# MASTER.net
KiCad netlist of a schematic drawn in Altium Designer
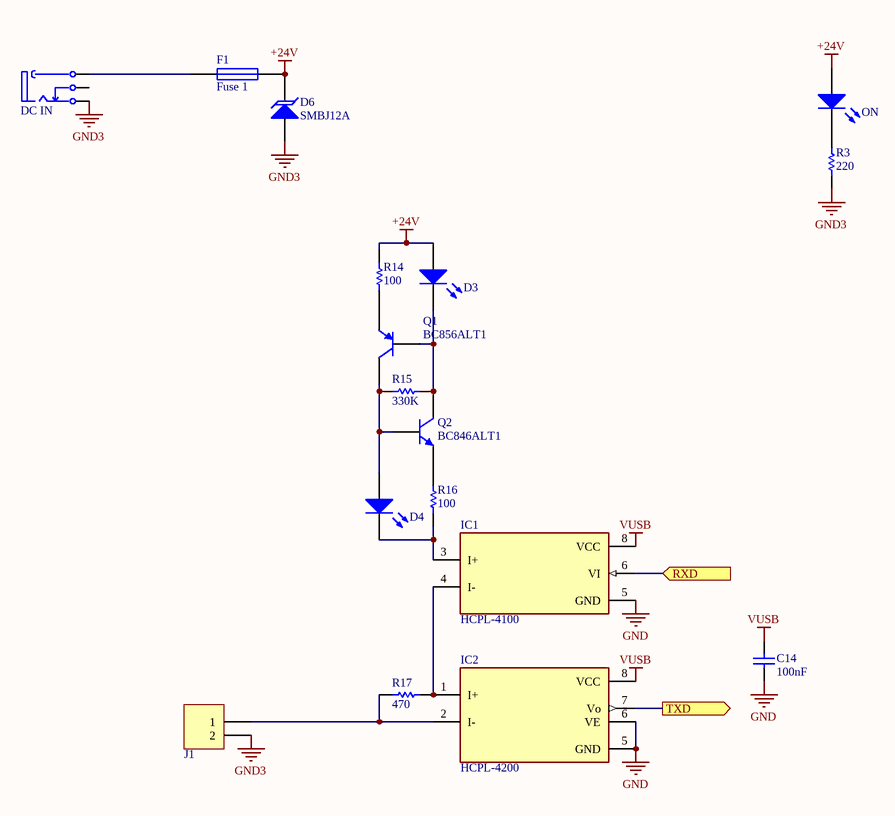
[diagram p0: MASTER.SchDoc]

(export (version "E")
  (design (tool "Eeschema 10.0.6"))
  (components
    (comp (ref "C14")
      (value "100nF")
      (footprint "C603")
      (description "Capacitor")
      (fields (field (name "DESIGNER") "Parsa Malekpour"))
      (libsource (lib "ParsaLibrary") (part "Cap"))
    )
    (comp (ref "D3") (value "LED") (footprint "LED-1206") (libsource (lib "ParsaLibrary") (part "LED")))
    (comp (ref "D4") (value "LED") (footprint "LED-1206") (libsource (lib "ParsaLibrary") (part "LED")))
    (comp (ref "D6")
      (value "SMBJ12A")
      (footprint "DO-214AA")
      (description "Surface Mount Transient Voltage Suppressors Diode")
      (libsource (lib "ParsaLibrary") (part "SMBJxxA"))
    )
    (comp (ref "DC IN")
      (value "JACK")
      (footprint "jack-dc")
      (libsource (lib "ParsaLibrary") (part "JACK-DC"))
    )
    (comp (ref "F1")
      (value "Fuse 1")
      (footprint "PTC-0805")
      (description "Fuse")
      (fields (field (name "PUBLISHER") "Altium Limited"))
      (libsource (lib "Miscellaneous Devices") (part "Fuse 1"))
    )
    (comp (ref "IC1")
      (value "HCPL-4100")
      (footprint "PARSALIBRARY:DIP-8")
      (description "<b>Isolation Amplifer</b><p> Source: http://www.avagotech.com/docs/AV02-0410EN")
      (fields (field (name "MF") "{'manufacturer': u'Broadcom Limited'}"))
      (libsource (lib "ParsaLibrary") (part "HCPL-4100"))
    )
    (comp (ref "IC2")
      (value "HCPL-4200")
      (footprint "PARSALIBRARY:DIP-8")
      (description "Optically Coupled 20 mA Current Loop Receiver")
      (fields (field (name "MF") "{'manufacturer': u'Broadcom Limited'}") (field (name "MP") "HCPL-4100"))
      (libsource (lib "ParsaLibrary") (part "HCPL-4200"))
    )
    (comp (ref "J1") (value "CONN-2") (footprint "XH-2") (libsource (lib "ParsaLibrary") (part "CONN-2")))
    (comp (ref "ON") (value "LED") (footprint "LED-1206") (libsource (lib "ParsaLibrary") (part "LED")))
    (comp (ref "Q1")
      (value "BC856ALT1")
      (footprint "SOT-23")
      (description "General Purpose Transistor PNP Silicon")
      (fields (field (name "PUBLISHER") "Altium Limited"))
      (libsource (lib "Motorola Discrete BJT") (part "BC856ALT1"))
    )
    (comp (ref "Q2")
      (value "BC846ALT1")
      (footprint "SOT-23")
      (description "General Purpose Transistor NPN Silicon")
      (fields (field (name "PUBLISHER") "Altium Limited"))
      (libsource (lib "Motorola Discrete BJT") (part "BC846ALT1"))
    )
    (comp (ref "R3")
      (value "220")
      (footprint "R805")
      (description "Resistor")
      (fields (field (name "DESIGNER") "Parsa Malekpour"))
      (libsource (lib "ParsaLibrary") (part "Resistor"))
    )
    (comp (ref "R14")
      (value "100")
      (footprint "R805")
      (description "Resistor")
      (fields (field (name "DESIGNER") "Parsa Malekpour"))
      (libsource (lib "ParsaLibrary") (part "Resistor"))
    )
    (comp (ref "R15")
      (value "330K")
      (footprint "R805")
      (description "Resistor")
      (fields (field (name "DESIGNER") "Parsa Malekpour"))
      (libsource (lib "ParsaLibrary") (part "Resistor"))
    )
    (comp (ref "R16")
      (value "100")
      (footprint "R805")
      (description "Resistor")
      (fields (field (name "DESIGNER") "Parsa Malekpour"))
      (libsource (lib "ParsaLibrary") (part "Resistor"))
    )
    (comp (ref "R17")
      (value "470")
      (footprint "R805")
      (description "Resistor")
      (fields (field (name "DESIGNER") "Parsa Malekpour"))
      (libsource (lib "ParsaLibrary") (part "Resistor"))
    )
  )
  (nets
    (net (code "1") (name "+24V") (class "Default")
      (node (ref "D3") (pin "1") (pinfunction "A_1") (pintype "passive"))
      (node (ref "D6") (pin "2") (pinfunction "K_2") (pintype "passive"))
      (node (ref "F1") (pin "2") (pinfunction "2_2") (pintype "passive"))
      (node (ref "ON") (pin "1") (pinfunction "A_1") (pintype "passive"))
      (node (ref "R14") (pin "2") (pinfunction "2_2") (pintype "passive"))
    )
    (net (code "2") (name "/RXD") (class "Default")
      (node (ref "IC1") (pin "6") (pinfunction "VI_6") (pintype "input"))
    )
    (net (code "3") (name "/TXD") (class "Default")
      (node (ref "IC2") (pin "7") (pinfunction "Vo_7") (pintype "output"))
    )
    (net (code "4") (name "GND") (class "Default")
      (node (ref "C14") (pin "1") (pinfunction "1_1") (pintype "passive"))
      (node (ref "IC1") (pin "5") (pinfunction "GND_5") (pintype "power_in"))
      (node (ref "IC2") (pin "5") (pinfunction "GND_5") (pintype "power_in"))
      (node (ref "IC2") (pin "6") (pinfunction "VE_6") (pintype "power_in"))
    )
    (net (code "5") (name "GND3") (class "Default")
      (node (ref "D6") (pin "1") (pinfunction "A_1") (pintype "passive"))
      (node (ref "DC IN") (pin "3") (pinfunction "sleeve_3") (pintype "power_in"))
      (node (ref "J1") (pin "2") (pinfunction "2_2") (pintype "passive"))
      (node (ref "R3") (pin "1") (pinfunction "1_1") (pintype "passive"))
    )
    (net (code "6") (name "Net-(D3-K)") (class "Default")
      (node (ref "D3") (pin "2") (pinfunction "K_2") (pintype "passive"))
      (node (ref "Q1") (pin "1") (pinfunction "B_1") (pintype "passive"))
      (node (ref "Q2") (pin "3") (pinfunction "C_3") (pintype "passive"))
      (node (ref "R15") (pin "1") (pinfunction "1_1") (pintype "passive"))
    )
    (net (code "7") (name "Net-(D4-A)") (class "Default")
      (node (ref "D4") (pin "1") (pinfunction "A_1") (pintype "passive"))
      (node (ref "Q1") (pin "3") (pinfunction "C_3") (pintype "passive"))
      (node (ref "Q2") (pin "1") (pinfunction "B_1") (pintype "passive"))
      (node (ref "R15") (pin "2") (pinfunction "2_2") (pintype "passive"))
    )
    (net (code "8") (name "Net-(D4-K)") (class "Default")
      (node (ref "D4") (pin "2") (pinfunction "K_2") (pintype "passive"))
      (node (ref "IC1") (pin "3") (pinfunction "I+_3") (pintype "power_in"))
      (node (ref "R16") (pin "1") (pinfunction "1_1") (pintype "passive"))
    )
    (net (code "9") (name "Net-(DC IN-tip)") (class "Default")
      (node (ref "DC IN") (pin "2") (pinfunction "tip_2") (pintype "power_in"))
      (node (ref "F1") (pin "1") (pinfunction "1_1") (pintype "passive"))
    )
    (net (code "10") (name "Net-(IC1-I-)") (class "Default")
      (node (ref "IC1") (pin "4") (pinfunction "I-_4") (pintype "power_in"))
      (node (ref "IC2") (pin "1") (pinfunction "I+_1") (pintype "power_in"))
      (node (ref "R17") (pin "2") (pinfunction "2_2") (pintype "passive"))
    )
    (net (code "11") (name "Net-(IC2-I-)") (class "Default")
      (node (ref "IC2") (pin "2") (pinfunction "I-_2") (pintype "power_in"))
      (node (ref "J1") (pin "1") (pinfunction "1_1") (pintype "passive"))
      (node (ref "R17") (pin "1") (pinfunction "1_1") (pintype "passive"))
    )
    (net (code "12") (name "Net-(ON-K)") (class "Default")
      (node (ref "ON") (pin "2") (pinfunction "K_2") (pintype "passive"))
      (node (ref "R3") (pin "2") (pinfunction "2_2") (pintype "passive"))
    )
    (net (code "13") (name "Net-(Q1-E)") (class "Default")
      (node (ref "Q1") (pin "2") (pinfunction "E_2") (pintype "passive"))
      (node (ref "R14") (pin "1") (pinfunction "1_1") (pintype "passive"))
    )
    (net (code "14") (name "Net-(Q2-E)") (class "Default")
      (node (ref "Q2") (pin "2") (pinfunction "E_2") (pintype "passive"))
      (node (ref "R16") (pin "2") (pinfunction "2_2") (pintype "passive"))
    )
    (net (code "15") (name "VUSB") (class "Default")
      (node (ref "C14") (pin "2") (pinfunction "2_2") (pintype "passive"))
      (node (ref "IC1") (pin "8") (pinfunction "VCC_8") (pintype "power_in"))
      (node (ref "IC2") (pin "8") (pinfunction "VCC_8") (pintype "power_in"))
    )
    (net (code "16") (name "unconnected-(DC IN-det-Pad1)") (class "Default")
      (node (ref "DC IN") (pin "1") (pinfunction "det_1") (pintype "passive"))
    )
  )
)
